# SpinMeter.net
KiCad netlist of a schematic drawn in EAGLE
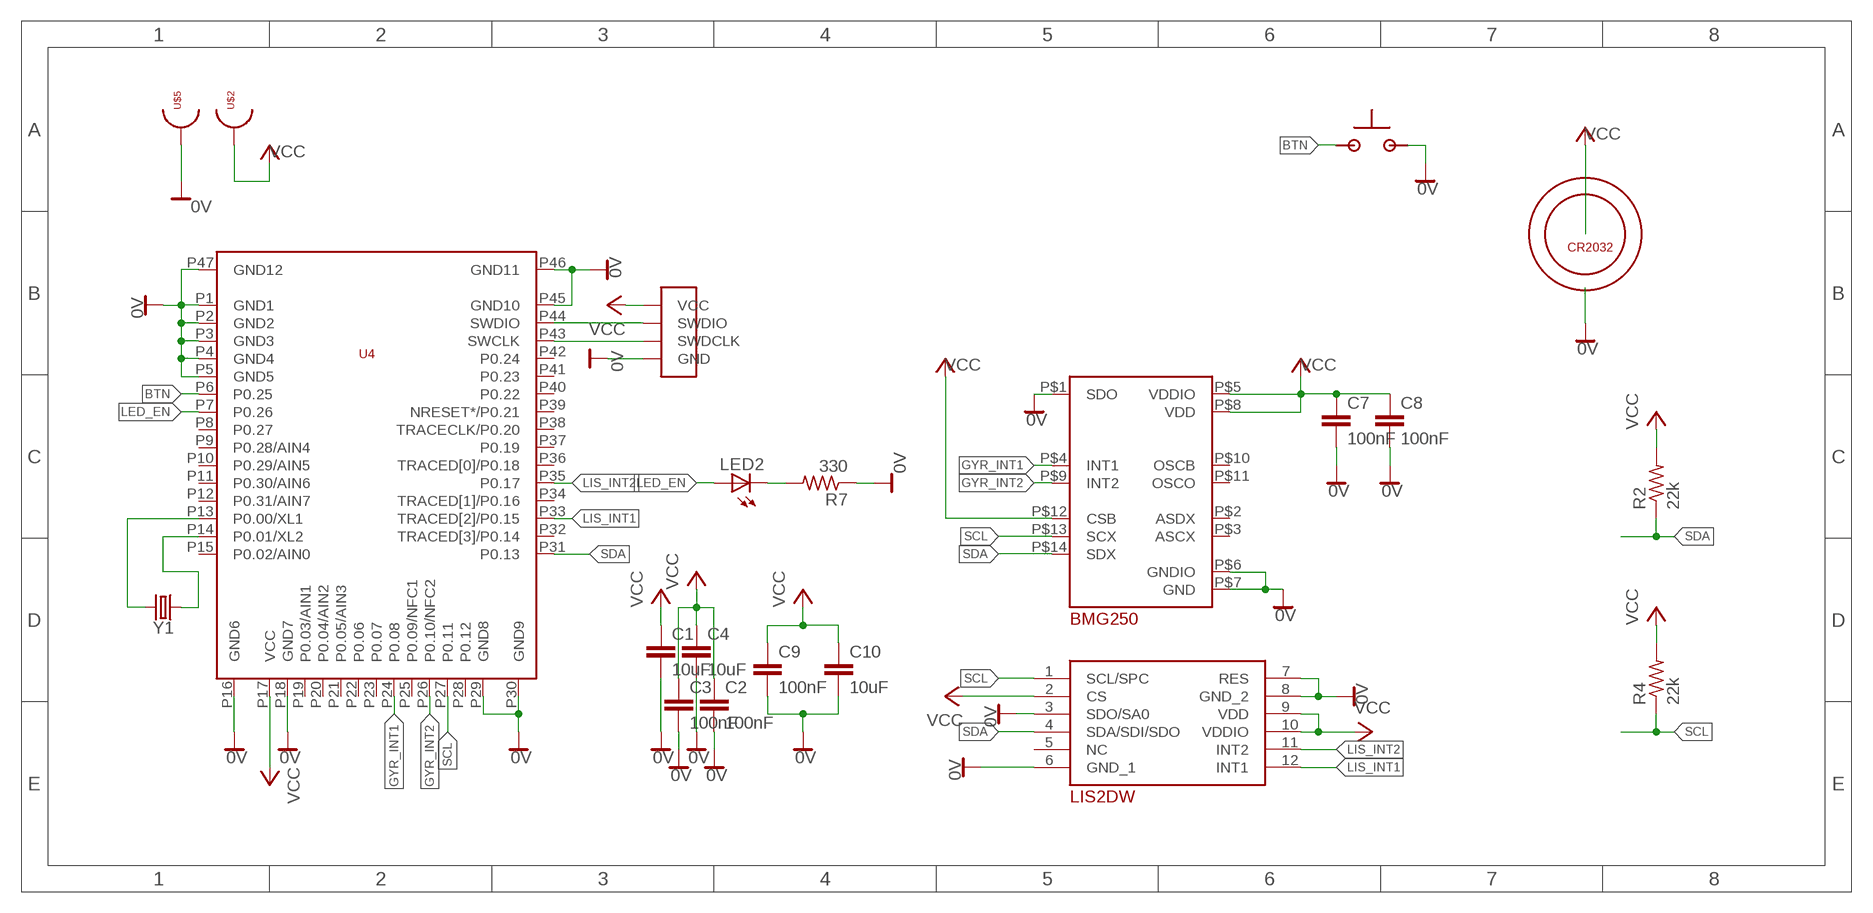
[diagram p0: schematic, sheet 1]

(export (version "E")
  (design (tool "Eeschema 10.0.6"))
  (components
    (comp (ref "C1")
      (value "10uF")
      (footprint "eagle-import:C0603")
      (libsource (lib "eagle-import") (part "C-EUC0603"))
    )
    (comp (ref "C2")
      (value "100nF")
      (footprint "eagle-import:C0603")
      (libsource (lib "eagle-import") (part "C-EUC0603"))
    )
    (comp (ref "C3")
      (value "100nF")
      (footprint "eagle-import:C0603")
      (libsource (lib "eagle-import") (part "C-EUC0603"))
    )
    (comp (ref "C4")
      (value "10uF")
      (footprint "eagle-import:C0603")
      (libsource (lib "eagle-import") (part "C-EUC0603"))
    )
    (comp (ref "C7")
      (value "100nF")
      (footprint "eagle-import:C0603")
      (libsource (lib "eagle-import") (part "C-EUC0603"))
    )
    (comp (ref "C8")
      (value "100nF")
      (footprint "eagle-import:C0603")
      (libsource (lib "eagle-import") (part "C-EUC0603"))
    )
    (comp (ref "C9")
      (value "100nF")
      (footprint "eagle-import:C0603")
      (libsource (lib "eagle-import") (part "C-EUC0603"))
    )
    (comp (ref "C10")
      (value "10uF")
      (footprint "eagle-import:C0603")
      (libsource (lib "eagle-import") (part "C-EUC0603"))
    )
    (comp (ref "IC1")
      (value "LIS2DW12TR")
      (footprint "eagle-import:LGA-12")
      (fields (field (name "MOUSER_PART_NUMBER") "511-LIS2DW12TR"))
      (libsource (lib "eagle-import") (part "LIS2DW12TR"))
    )
    (comp (ref "LED2")
      (value "LEDCHIP-LED0603")
      (footprint "eagle-import:CHIP-LED0603")
      (libsource (lib "eagle-import") (part "LEDCHIP-LED0603"))
    )
    (comp (ref "R2")
      (value "22k")
      (footprint "eagle-import:R0603")
      (libsource (lib "eagle-import") (part "R-US_R0603"))
    )
    (comp (ref "R4")
      (value "22k")
      (footprint "eagle-import:R0603")
      (libsource (lib "eagle-import") (part "R-US_R0603"))
    )
    (comp (ref "R7")
      (value "330")
      (footprint "eagle-import:R0603")
      (libsource (lib "eagle-import") (part "R-US_R0603"))
    )
    (comp (ref "U$1")
      (value "PROG_SMD")
      (footprint "eagle-import:PROG_SMD")
      (libsource (lib "eagle-import") (part "PROG_SMD"))
    )
    (comp (ref "U$2")
      (value "TESTPOINT_22")
      (footprint "eagle-import:TESTPOINT_22")
      (libsource (lib "eagle-import") (part "TESTPOINT_22"))
    )
    (comp (ref "U$5")
      (value "TESTPOINT_22")
      (footprint "eagle-import:TESTPOINT_22")
      (libsource (lib "eagle-import") (part "TESTPOINT_22"))
    )
    (comp (ref "U$10")
      (value "SKRMAAE010")
      (footprint "eagle-import:SKRMAAE010")
      (libsource (lib "eagle-import") (part "SKRMAAE010"))
    )
    (comp (ref "U1")
      (value "BMG250")
      (footprint "eagle-import:LGA14")
      (libsource (lib "eagle-import") (part "BMG250"))
    )
    (comp (ref "U3")
      (value "BAT-HLD-001-THM")
      (footprint "eagle-import:BATHLD001THM")
      (fields (field (name "MOUSER_PART_NUMBER") "712-BAT-HLD-001-THM"))
      (libsource (lib "eagle-import") (part "BAT-HLD-001-THM"))
    )
    (comp (ref "U4")
      (value "BMD-300")
      (footprint "eagle-import:BMD-300")
      (libsource (lib "eagle-import") (part "BMD-300"))
    )
    (comp (ref "Y1")
      (value "CRYSTALSMD-3.2X1.5")
      (footprint "eagle-import:CRYSTAL-SMD-3.2X1.5MM")
      (libsource (lib "eagle-import") (part "CRYSTALSMD-3.2X1.5"))
    )
  )
  (nets
    (net (code "1") (name "0V") (class "Default")
      (node (ref "C1") (pin "2") (pinfunction "2_2") (pintype "passive"))
      (node (ref "C10") (pin "2") (pinfunction "2_2") (pintype "passive"))
      (node (ref "C2") (pin "2") (pinfunction "2_2") (pintype "passive"))
      (node (ref "C3") (pin "2") (pinfunction "2_2") (pintype "passive"))
      (node (ref "C4") (pin "2") (pinfunction "2_2") (pintype "passive"))
      (node (ref "C7") (pin "2") (pinfunction "2_2") (pintype "passive"))
      (node (ref "C8") (pin "2") (pinfunction "2_2") (pintype "passive"))
      (node (ref "C9") (pin "2") (pinfunction "2_2") (pintype "passive"))
      (node (ref "IC1") (pin "3") (pinfunction "SDO/SA0_3") (pintype "bidirectional"))
      (node (ref "IC1") (pin "6") (pinfunction "GND_1_6") (pintype "bidirectional"))
      (node (ref "IC1") (pin "7") (pinfunction "RES_7") (pintype "bidirectional"))
      (node (ref "IC1") (pin "8") (pinfunction "GND_2_8") (pintype "bidirectional"))
      (node (ref "R7") (pin "1") (pinfunction "1_1") (pintype "passive"))
      (node (ref "U$1") (pin "GND") (pinfunction "GND_GND") (pintype "bidirectional"))
      (node (ref "U$10") (pin "P$2") (pinfunction "P$2_P$2") (pintype "bidirectional"))
      (node (ref "U$10") (pin "P$4") (pinfunction "P$2_P$4") (pintype "bidirectional"))
      (node (ref "U$5") (pin "P$1") (pinfunction "P$1_P$1") (pintype "bidirectional"))
      (node (ref "U1") (pin "P$1") (pinfunction "SDO_P$1") (pintype "bidirectional"))
      (node (ref "U1") (pin "P$6") (pinfunction "GNDIO_P$6") (pintype "power_in"))
      (node (ref "U1") (pin "P$7") (pinfunction "GND_P$7") (pintype "power_in"))
      (node (ref "U3") (pin "5") (pinfunction "-_5") (pintype "power_in"))
      (node (ref "U4") (pin "P1") (pinfunction "GND1_P1") (pintype "bidirectional"))
      (node (ref "U4") (pin "P16") (pinfunction "GND6_P16") (pintype "bidirectional"))
      (node (ref "U4") (pin "P18") (pinfunction "GND7_P18") (pintype "bidirectional"))
      (node (ref "U4") (pin "P2") (pinfunction "GND2_P2") (pintype "bidirectional"))
      (node (ref "U4") (pin "P29") (pinfunction "GND8_P29") (pintype "bidirectional"))
      (node (ref "U4") (pin "P3") (pinfunction "GND3_P3") (pintype "bidirectional"))
      (node (ref "U4") (pin "P30") (pinfunction "GND9_P30") (pintype "bidirectional"))
      (node (ref "U4") (pin "P4") (pinfunction "GND4_P4") (pintype "bidirectional"))
      (node (ref "U4") (pin "P45") (pinfunction "GND10_P45") (pintype "bidirectional"))
      (node (ref "U4") (pin "P46") (pinfunction "GND11_P46") (pintype "bidirectional"))
      (node (ref "U4") (pin "P47") (pinfunction "GND12_P47") (pintype "bidirectional"))
      (node (ref "U4") (pin "P5") (pinfunction "GND5_P5") (pintype "bidirectional"))
    )
    (net (code "2") (name "BTN") (class "Default")
      (node (ref "U$10") (pin "P$1") (pinfunction "P$1_P$1") (pintype "bidirectional"))
      (node (ref "U$10") (pin "P$3") (pinfunction "P$1_P$3") (pintype "bidirectional"))
      (node (ref "U4") (pin "P6") (pinfunction "P0.25_P6") (pintype "bidirectional"))
    )
    (net (code "3") (name "GYR_INT1") (class "Default")
      (node (ref "U1") (pin "P$4") (pinfunction "INT1_P$4") (pintype "bidirectional"))
      (node (ref "U4") (pin "P24") (pinfunction "P0.08_P24") (pintype "bidirectional"))
    )
    (net (code "4") (name "GYR_INT2") (class "Default")
      (node (ref "U1") (pin "P$9") (pinfunction "INT2_P$9") (pintype "bidirectional"))
      (node (ref "U4") (pin "P26") (pinfunction "P0.10/NFC2_P26") (pintype "bidirectional"))
    )
    (net (code "5") (name "LED_EN") (class "Default")
      (node (ref "LED2") (pin "A") (pinfunction "A_A") (pintype "passive"))
      (node (ref "U4") (pin "P7") (pinfunction "P0.26_P7") (pintype "bidirectional"))
    )
    (net (code "6") (name "LIS_INT1") (class "Default")
      (node (ref "IC1") (pin "12") (pinfunction "INT1_12") (pintype "bidirectional"))
      (node (ref "U4") (pin "P33") (pinfunction "TRACED[2]/P0.15_P33") (pintype "bidirectional"))
    )
    (net (code "7") (name "LIS_INT2") (class "Default")
      (node (ref "IC1") (pin "11") (pinfunction "INT2_11") (pintype "bidirectional"))
      (node (ref "U4") (pin "P35") (pinfunction "P0.17_P35") (pintype "bidirectional"))
    )
    (net (code "8") (name "Net-(LED2-PadC)") (class "Default")
      (node (ref "LED2") (pin "C") (pinfunction "C_C") (pintype "passive"))
      (node (ref "R7") (pin "2") (pinfunction "2_2") (pintype "passive"))
    )
    (net (code "9") (name "Net-(U$1-SWDCLK)") (class "Default")
      (node (ref "U$1") (pin "PIN1") (pinfunction "SWDCLK_PIN1") (pintype "bidirectional"))
      (node (ref "U4") (pin "P43") (pinfunction "SWCLK_P43") (pintype "bidirectional"))
    )
    (net (code "10") (name "Net-(U$1-SWDIO)") (class "Default")
      (node (ref "U$1") (pin "PIN2") (pinfunction "SWDIO_PIN2") (pintype "bidirectional"))
      (node (ref "U4") (pin "P44") (pinfunction "SWDIO_P44") (pintype "bidirectional"))
    )
    (net (code "11") (name "Net-(U4-P0.00{slash}XL1)") (class "Default")
      (node (ref "U4") (pin "P13") (pinfunction "P0.00/XL1_P13") (pintype "bidirectional"))
      (node (ref "Y1") (pin "P$2") (pinfunction "2_P$2") (pintype "passive"))
    )
    (net (code "12") (name "Net-(U4-P0.01{slash}XL2)") (class "Default")
      (node (ref "U4") (pin "P14") (pinfunction "P0.01/XL2_P14") (pintype "bidirectional"))
      (node (ref "Y1") (pin "P$1") (pinfunction "1_P$1") (pintype "passive"))
    )
    (net (code "13") (name "SCL") (class "Default")
      (node (ref "IC1") (pin "1") (pinfunction "SCL/SPC_1") (pintype "bidirectional"))
      (node (ref "R4") (pin "1") (pinfunction "1_1") (pintype "passive"))
      (node (ref "U1") (pin "P$13") (pinfunction "SCX_P$13") (pintype "bidirectional"))
      (node (ref "U4") (pin "P27") (pinfunction "P0.11_P27") (pintype "bidirectional"))
    )
    (net (code "14") (name "SDA") (class "Default")
      (node (ref "IC1") (pin "4") (pinfunction "SDA/SDI/SDO_4") (pintype "bidirectional"))
      (node (ref "R2") (pin "1") (pinfunction "1_1") (pintype "passive"))
      (node (ref "U1") (pin "P$14") (pinfunction "SDX_P$14") (pintype "bidirectional"))
      (node (ref "U4") (pin "P31") (pinfunction "P0.13_P31") (pintype "bidirectional"))
    )
    (net (code "15") (name "VCC") (class "Default")
      (node (ref "C1") (pin "1") (pinfunction "1_1") (pintype "passive"))
      (node (ref "C10") (pin "1") (pinfunction "1_1") (pintype "passive"))
      (node (ref "C2") (pin "1") (pinfunction "1_1") (pintype "passive"))
      (node (ref "C3") (pin "1") (pinfunction "1_1") (pintype "passive"))
      (node (ref "C4") (pin "1") (pinfunction "1_1") (pintype "passive"))
      (node (ref "C7") (pin "1") (pinfunction "1_1") (pintype "passive"))
      (node (ref "C8") (pin "1") (pinfunction "1_1") (pintype "passive"))
      (node (ref "C9") (pin "1") (pinfunction "1_1") (pintype "passive"))
      (node (ref "IC1") (pin "10") (pinfunction "VDDIO_10") (pintype "bidirectional"))
      (node (ref "IC1") (pin "2") (pinfunction "CS_2") (pintype "bidirectional"))
      (node (ref "IC1") (pin "9") (pinfunction "VDD_9") (pintype "bidirectional"))
      (node (ref "R2") (pin "2") (pinfunction "2_2") (pintype "passive"))
      (node (ref "R4") (pin "2") (pinfunction "2_2") (pintype "passive"))
      (node (ref "U$1") (pin "VCC") (pinfunction "VCC_VCC") (pintype "bidirectional"))
      (node (ref "U$2") (pin "P$1") (pinfunction "P$1_P$1") (pintype "bidirectional"))
      (node (ref "U1") (pin "P$12") (pinfunction "CSB_P$12") (pintype "bidirectional"))
      (node (ref "U1") (pin "P$5") (pinfunction "VDDIO_P$5") (pintype "power_in"))
      (node (ref "U1") (pin "P$8") (pinfunction "VDD_P$8") (pintype "power_in"))
      (node (ref "U3") (pin "1") (pinfunction "+_1") (pintype "power_in"))
      (node (ref "U3") (pin "2") (pinfunction "+_2") (pintype "power_in"))
      (node (ref "U3") (pin "3") (pinfunction "+_3") (pintype "power_in"))
      (node (ref "U3") (pin "4") (pinfunction "+_4") (pintype "power_in"))
      (node (ref "U4") (pin "P17") (pinfunction "VCC_P17") (pintype "bidirectional"))
    )
    (net (code "16") (name "unconnected-(IC1-NC-Pad5)") (class "Default")
      (node (ref "IC1") (pin "5") (pinfunction "NC_5") (pintype "no_connect"))
    )
    (net (code "17") (name "unconnected-(U1-ASCX-PadP$3)") (class "Default")
      (node (ref "U1") (pin "P$3") (pinfunction "ASCX_P$3") (pintype "bidirectional"))
    )
    (net (code "18") (name "unconnected-(U1-ASDX-PadP$2)") (class "Default")
      (node (ref "U1") (pin "P$2") (pinfunction "ASDX_P$2") (pintype "bidirectional"))
    )
    (net (code "19") (name "unconnected-(U1-OSCB-PadP$10)") (class "Default")
      (node (ref "U1") (pin "P$10") (pinfunction "OSCB_P$10") (pintype "bidirectional"))
    )
    (net (code "20") (name "unconnected-(U1-OSCO-PadP$11)") (class "Default")
      (node (ref "U1") (pin "P$11") (pinfunction "OSCO_P$11") (pintype "bidirectional"))
    )
    (net (code "21") (name "unconnected-(U4-NRESET*{slash}P0.21-PadP39)") (class "Default")
      (node (ref "U4") (pin "P39") (pinfunction "NRESET*/P0.21_P39") (pintype "bidirectional"))
    )
    (net (code "22") (name "unconnected-(U4-P0.02{slash}AIN0-PadP15)") (class "Default")
      (node (ref "U4") (pin "P15") (pinfunction "P0.02/AIN0_P15") (pintype "bidirectional"))
    )
    (net (code "23") (name "unconnected-(U4-P0.03{slash}AIN1-PadP19)") (class "Default")
      (node (ref "U4") (pin "P19") (pinfunction "P0.03/AIN1_P19") (pintype "bidirectional"))
    )
    (net (code "24") (name "unconnected-(U4-P0.04{slash}AIN2-PadP20)") (class "Default")
      (node (ref "U4") (pin "P20") (pinfunction "P0.04/AIN2_P20") (pintype "bidirectional"))
    )
    (net (code "25") (name "unconnected-(U4-P0.05{slash}AIN3-PadP21)") (class "Default")
      (node (ref "U4") (pin "P21") (pinfunction "P0.05/AIN3_P21") (pintype "bidirectional"))
    )
    (net (code "26") (name "unconnected-(U4-P0.06-PadP22)") (class "Default")
      (node (ref "U4") (pin "P22") (pinfunction "P0.06_P22") (pintype "bidirectional"))
    )
    (net (code "27") (name "unconnected-(U4-P0.07-PadP23)") (class "Default")
      (node (ref "U4") (pin "P23") (pinfunction "P0.07_P23") (pintype "bidirectional"))
    )
    (net (code "28") (name "unconnected-(U4-P0.09{slash}NFC1-PadP25)") (class "Default")
      (node (ref "U4") (pin "P25") (pinfunction "P0.09/NFC1_P25") (pintype "bidirectional"))
    )
    (net (code "29") (name "unconnected-(U4-P0.12-PadP28)") (class "Default")
      (node (ref "U4") (pin "P28") (pinfunction "P0.12_P28") (pintype "bidirectional"))
    )
    (net (code "30") (name "unconnected-(U4-P0.19-PadP37)") (class "Default")
      (node (ref "U4") (pin "P37") (pinfunction "P0.19_P37") (pintype "bidirectional"))
    )
    (net (code "31") (name "unconnected-(U4-P0.22-PadP40)") (class "Default")
      (node (ref "U4") (pin "P40") (pinfunction "P0.22_P40") (pintype "bidirectional"))
    )
    (net (code "32") (name "unconnected-(U4-P0.23-PadP41)") (class "Default")
      (node (ref "U4") (pin "P41") (pinfunction "P0.23_P41") (pintype "bidirectional"))
    )
    (net (code "33") (name "unconnected-(U4-P0.24-PadP42)") (class "Default")
      (node (ref "U4") (pin "P42") (pinfunction "P0.24_P42") (pintype "bidirectional"))
    )
    (net (code "34") (name "unconnected-(U4-P0.27-PadP8)") (class "Default")
      (node (ref "U4") (pin "P8") (pinfunction "P0.27_P8") (pintype "bidirectional"))
    )
    (net (code "35") (name "unconnected-(U4-P0.28{slash}AIN4-PadP9)") (class "Default")
      (node (ref "U4") (pin "P9") (pinfunction "P0.28/AIN4_P9") (pintype "bidirectional"))
    )
    (net (code "36") (name "unconnected-(U4-P0.29{slash}AIN5-PadP10)") (class "Default")
      (node (ref "U4") (pin "P10") (pinfunction "P0.29/AIN5_P10") (pintype "bidirectional"))
    )
    (net (code "37") (name "unconnected-(U4-P0.30{slash}AIN6-PadP11)") (class "Default")
      (node (ref "U4") (pin "P11") (pinfunction "P0.30/AIN6_P11") (pintype "bidirectional"))
    )
    (net (code "38") (name "unconnected-(U4-P0.31{slash}AIN7-PadP12)") (class "Default")
      (node (ref "U4") (pin "P12") (pinfunction "P0.31/AIN7_P12") (pintype "bidirectional"))
    )
    (net (code "39") (name "unconnected-(U4-TRACECLK{slash}P0.20-PadP38)") (class "Default")
      (node (ref "U4") (pin "P38") (pinfunction "TRACECLK/P0.20_P38") (pintype "bidirectional"))
    )
    (net (code "40") (name "unconnected-(U4-TRACED[0]{slash}P0.18-PadP36)") (class "Default")
      (node (ref "U4") (pin "P36") (pinfunction "TRACED[0]/P0.18_P36") (pintype "bidirectional"))
    )
    (net (code "41") (name "unconnected-(U4-TRACED[1]{slash}P0.16-PadP34)") (class "Default")
      (node (ref "U4") (pin "P34") (pinfunction "TRACED[1]/P0.16_P34") (pintype "bidirectional"))
    )
    (net (code "42") (name "unconnected-(U4-TRACED[3]{slash}P0.14-PadP32)") (class "Default")
      (node (ref "U4") (pin "P32") (pinfunction "TRACED[3]/P0.14_P32") (pintype "bidirectional"))
    )
  )
)
